# Differentiator.net
KiCad netlist of a schematic drawn in Altium Designer
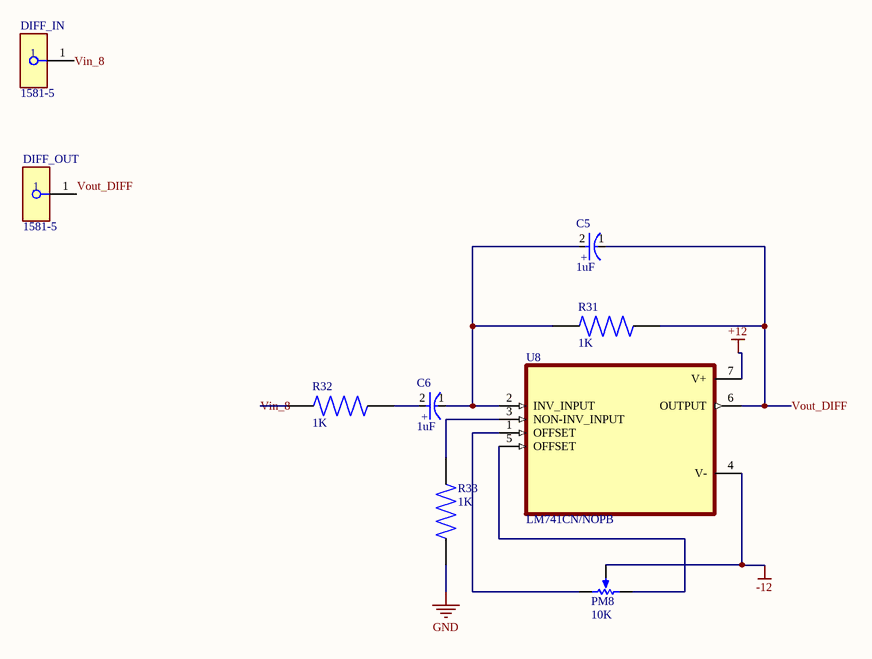
[diagram p0: Differentiator.SchDoc]

(export (version "E")
  (design (tool "Eeschema 10.0.6"))
  (components
    (comp (ref "C5")
      (value "1uF")
      (footprint "FP-ECA-2CHG010I-MFG")
      (description "CAP ALUM 1UF 20% 160V RADIAL")
      (fields (field (name "TOLERANCE") "20%"))
      (libsource (lib "Altium Content Vault") (part "a00bbbee19879c290e62620ae7e47b1"))
    )
    (comp (ref "C6")
      (value "1uF")
      (footprint "FP-ECA-2CHG010I-MFG")
      (description "CAP ALUM 1UF 20% 160V RADIAL")
      (fields (field (name "TOLERANCE") "20%"))
      (libsource (lib "Altium Content Vault") (part "a00bbbee19879c290e62620ae7e47b1"))
    )
    (comp (ref "DIFF_IN")
      (value "1581-5")
      (footprint "FP-1581-5-MFG")
      (description "CONN BANANA JACK TURRET GREEN")
      (libsource (lib "Altium Content Vault") (part "c5c826e0c4b67fe3b42ef77f2d4decc"))
    )
    (comp (ref "DIFF_OUT")
      (value "1581-5")
      (footprint "FP-1581-5-MFG")
      (description "CONN BANANA JACK TURRET GREEN")
      (libsource (lib "Altium Content Vault") (part "c5c826e0c4b67fe3b42ef77f2d4decc"))
    )
    (comp (ref "PM8")
      (value "10K")
      (footprint "PCBComponent_1")
      (libsource (lib "Integrated_Library1") (part "Component_1"))
    )
    (comp (ref "R31")
      (value "1K")
      (footprint "RESAD1100W55L680D260")
      (description "1.07 kOhms Â±1% 0.25W, 1/4W Through Hole Resistor Axial - Metal Film")
      (fields (field (name "MF") "Yageo") (field (name "MP") "MFR-25FBF52-1K"))
      (libsource (lib "MFR-25FBF52-1K") (part "MFR-25FBF52-1K"))
    )
    (comp (ref "R32")
      (value "1K")
      (footprint "RESAD1100W55L680D260")
      (description "1.07 kOhms Â±1% 0.25W, 1/4W Through Hole Resistor Axial - Metal Film")
      (fields (field (name "MF") "Yageo") (field (name "MP") "MFR-25FBF52-1K"))
      (libsource (lib "MFR-25FBF52-1K") (part "MFR-25FBF52-1K"))
    )
    (comp (ref "R33")
      (value "1K")
      (footprint "RESAD1100W55L680D260")
      (description "1.07 kOhms Â±1% 0.25W, 1/4W Through Hole Resistor Axial - Metal Film")
      (fields (field (name "MF") "Yageo") (field (name "MP") "MFR-25FBF52-1K"))
      (libsource (lib "MFR-25FBF52-1K") (part "MFR-25FBF52-1K"))
    )
    (comp (ref "U8")
      (value "LM741CN/NOPB")
      (footprint "DIP794W45P254L959H508Q8")
      (description "Single, 44-V, 1-MHz operational amplifier")
      (fields (field (name "MF") "Texas Instruments"))
      (libsource (lib "LM741CN_NOPB (1)") (part "LM741CN/NOPB"))
    )
  )
  (nets
    (net (code "1") (name "+12") (class "Default")
      (node (ref "U8") (pin "7") (pinfunction "V+_7") (pintype "power_in"))
    )
    (net (code "2") (name "-12") (class "Default")
      (node (ref "PM8") (pin "2") (pinfunction "S_2") (pintype "passive"))
      (node (ref "U8") (pin "4") (pinfunction "V-_4") (pintype "power_in"))
    )
    (net (code "3") (name "/Vin_8") (class "Default")
      (node (ref "DIFF_IN") (pin "1") (pinfunction "1_1") (pintype "passive"))
      (node (ref "R32") (pin "1") (pinfunction "1_1") (pintype "passive"))
    )
    (net (code "4") (name "/Vout_DIFF") (class "Default")
      (node (ref "C5") (pin "1") (pinfunction "C_1") (pintype "passive"))
      (node (ref "DIFF_OUT") (pin "1") (pinfunction "1_1") (pintype "passive"))
      (node (ref "R31") (pin "2") (pinfunction "2_2") (pintype "passive"))
      (node (ref "U8") (pin "6") (pinfunction "OUTPUT_6") (pintype "output"))
    )
    (net (code "5") (name "GND") (class "Default")
      (node (ref "R33") (pin "1") (pinfunction "1_1") (pintype "passive"))
    )
    (net (code "6") (name "Net-(C5-A)") (class "Default")
      (node (ref "C5") (pin "2") (pinfunction "A_2") (pintype "passive"))
      (node (ref "C6") (pin "1") (pinfunction "C_1") (pintype "passive"))
      (node (ref "R31") (pin "1") (pinfunction "1_1") (pintype "passive"))
      (node (ref "U8") (pin "2") (pinfunction "INV_INPUT_2") (pintype "input"))
    )
    (net (code "7") (name "Net-(C6-A)") (class "Default")
      (node (ref "C6") (pin "2") (pinfunction "A_2") (pintype "passive"))
      (node (ref "R32") (pin "2") (pinfunction "2_2") (pintype "passive"))
    )
    (net (code "8") (name "Net-(PM8-CCW)") (class "Default")
      (node (ref "PM8") (pin "1") (pinfunction "CCW_1") (pintype "passive"))
      (node (ref "U8") (pin "5") (pinfunction "OFFSET_5") (pintype "input"))
    )
    (net (code "9") (name "Net-(PM8-CW)") (class "Default")
      (node (ref "PM8") (pin "3") (pinfunction "CW_3") (pintype "passive"))
      (node (ref "U8") (pin "1") (pinfunction "OFFSET_1") (pintype "input"))
    )
    (net (code "10") (name "Net-(U8-NON-INV_INPUT)") (class "Default")
      (node (ref "R33") (pin "2") (pinfunction "2_2") (pintype "passive"))
      (node (ref "U8") (pin "3") (pinfunction "NON-INV_INPUT_3") (pintype "input"))
    )
  )
)
